# otl.net
KiCad netlist of a schematic drawn in EAGLE
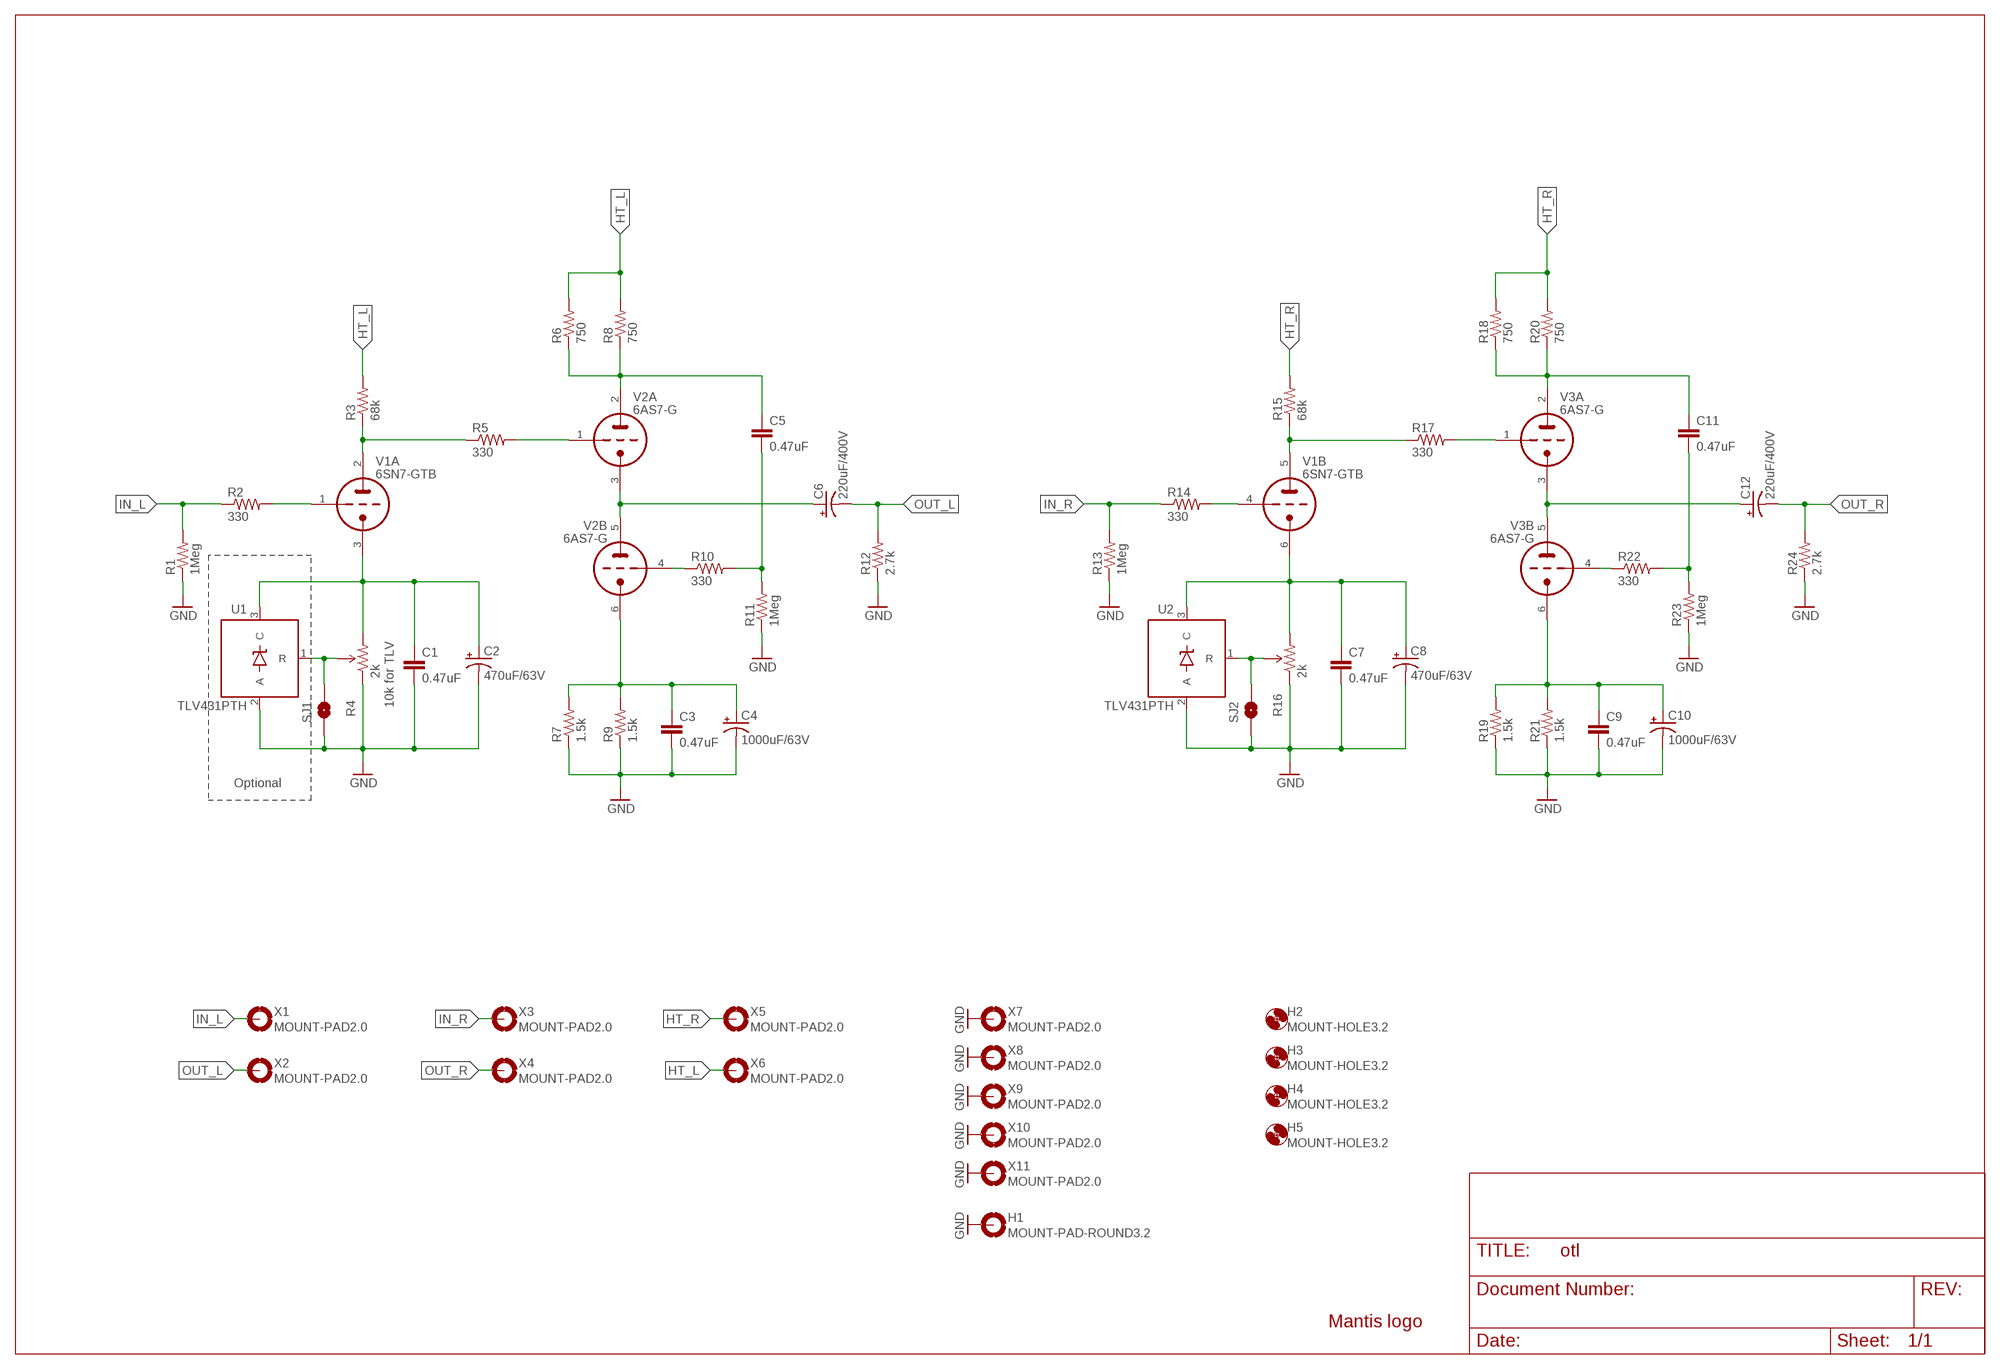
[diagram p0: schematic, sheet 1]

(export (version "E")
  (design (tool "Eeschema 10.0.6"))
  (components
    (comp (ref "C1")
      (value "0.47uF")
      (footprint "eagle-import:C5B5.5")
      (libsource (lib "eagle-import") (part "C5/5.5"))
    )
    (comp (ref "C2")
      (value "470uF/63V")
      (footprint "eagle-import:CPOL-RADIAL-16_7.5")
      (libsource (lib "eagle-import") (part "CAP_POLPTH-16/7.5"))
    )
    (comp (ref "C3")
      (value "0.47uF")
      (footprint "eagle-import:C5B5.5")
      (libsource (lib "eagle-import") (part "C5/5.5"))
    )
    (comp (ref "C4")
      (value "1000uF/63V")
      (footprint "eagle-import:CPOL-RADIAL-16_7.5")
      (libsource (lib "eagle-import") (part "CAP_POLPTH-16/7.5"))
    )
    (comp (ref "C5")
      (value "0.47uF")
      (footprint "eagle-import:C22.5B11")
      (libsource (lib "eagle-import") (part "C22/11"))
    )
    (comp (ref "C6")
      (value "220uF/400V")
      (footprint "eagle-import:CPOL-RADIAL-25_12.5")
      (libsource (lib "eagle-import") (part "CAP_POLPTH-25/12.5"))
    )
    (comp (ref "C7")
      (value "0.47uF")
      (footprint "eagle-import:C5B5.5")
      (libsource (lib "eagle-import") (part "C5/5.5"))
    )
    (comp (ref "C8")
      (value "470uF/63V")
      (footprint "eagle-import:CPOL-RADIAL-16_7.5")
      (libsource (lib "eagle-import") (part "CAP_POLPTH-16/7.5"))
    )
    (comp (ref "C9")
      (value "0.47uF")
      (footprint "eagle-import:C5B5.5")
      (libsource (lib "eagle-import") (part "C5/5.5"))
    )
    (comp (ref "C10")
      (value "1000uF/63V")
      (footprint "eagle-import:CPOL-RADIAL-16_7.5")
      (libsource (lib "eagle-import") (part "CAP_POLPTH-16/7.5"))
    )
    (comp (ref "C11")
      (value "0.47uF")
      (footprint "eagle-import:C22.5B11")
      (libsource (lib "eagle-import") (part "C22/11"))
    )
    (comp (ref "C12")
      (value "220uF/400V")
      (footprint "eagle-import:CPOL-RADIAL-25_12.5")
      (libsource (lib "eagle-import") (part "CAP_POLPTH-25/12.5"))
    )
    (comp (ref "H1")
      (value "MOUNT-PAD-ROUND3.2")
      (footprint "eagle-import:3,2-PAD")
      (libsource (lib "eagle-import") (part "MOUNT-PAD-ROUND3.2"))
    )
    (comp (ref "H2")
      (value "MOUNT-HOLE3.2")
      (footprint "eagle-import:3,2")
      (libsource (lib "eagle-import") (part "MOUNT-HOLE3.2"))
    )
    (comp (ref "H3")
      (value "MOUNT-HOLE3.2")
      (footprint "eagle-import:3,2")
      (libsource (lib "eagle-import") (part "MOUNT-HOLE3.2"))
    )
    (comp (ref "H4")
      (value "MOUNT-HOLE3.2")
      (footprint "eagle-import:3,2")
      (libsource (lib "eagle-import") (part "MOUNT-HOLE3.2"))
    )
    (comp (ref "H5")
      (value "MOUNT-HOLE3.2")
      (footprint "eagle-import:3,2")
      (libsource (lib "eagle-import") (part "MOUNT-HOLE3.2"))
    )
    (comp (ref "LOGO1")
      (value "LOGO-MANTIS")
      (footprint "eagle-import:LOGO-MANTIS")
      (libsource (lib "eagle-import") (part "LOGO-MANTIS"))
    )
    (comp (ref "R1")
      (value "1Meg")
      (footprint "eagle-import:AXIAL-0.4")
      (libsource (lib "eagle-import") (part "RESISTORPTH-1/4W"))
    )
    (comp (ref "R2")
      (value "330")
      (footprint "eagle-import:AXIAL-0.4")
      (libsource (lib "eagle-import") (part "RESISTORPTH-1/4W"))
    )
    (comp (ref "R3")
      (value "68k")
      (footprint "eagle-import:AXIAL-0.8")
      (libsource (lib "eagle-import") (part "RESISTORPTH-2W"))
    )
    (comp (ref "R4")
      (value "2k")
      (footprint "eagle-import:3362U-2")
      (libsource (lib "eagle-import") (part "TRIMPOT3362U-2"))
    )
    (comp (ref "R5")
      (value "330")
      (footprint "eagle-import:AXIAL-0.4")
      (libsource (lib "eagle-import") (part "RESISTORPTH-1/4W"))
    )
    (comp (ref "R6")
      (value "750")
      (footprint "eagle-import:AXIAL-0.8")
      (libsource (lib "eagle-import") (part "RESISTORPTH-2W"))
    )
    (comp (ref "R7")
      (value "1.5k")
      (footprint "eagle-import:AXIAL-0.8")
      (libsource (lib "eagle-import") (part "RESISTORPTH-2W"))
    )
    (comp (ref "R8")
      (value "750")
      (footprint "eagle-import:AXIAL-0.8")
      (libsource (lib "eagle-import") (part "RESISTORPTH-2W"))
    )
    (comp (ref "R9")
      (value "1.5k")
      (footprint "eagle-import:AXIAL-0.8")
      (libsource (lib "eagle-import") (part "RESISTORPTH-2W"))
    )
    (comp (ref "R10")
      (value "330")
      (footprint "eagle-import:AXIAL-0.4")
      (libsource (lib "eagle-import") (part "RESISTORPTH-1/4W"))
    )
    (comp (ref "R11")
      (value "1Meg")
      (footprint "eagle-import:AXIAL-0.4")
      (libsource (lib "eagle-import") (part "RESISTORPTH-1/4W"))
    )
    (comp (ref "R12")
      (value "2.7k")
      (footprint "eagle-import:AXIAL-0.4")
      (libsource (lib "eagle-import") (part "RESISTORPTH-1/4W"))
    )
    (comp (ref "R13")
      (value "1Meg")
      (footprint "eagle-import:AXIAL-0.4")
      (libsource (lib "eagle-import") (part "RESISTORPTH-1/4W"))
    )
    (comp (ref "R14")
      (value "330")
      (footprint "eagle-import:AXIAL-0.4")
      (libsource (lib "eagle-import") (part "RESISTORPTH-1/4W"))
    )
    (comp (ref "R15")
      (value "68k")
      (footprint "eagle-import:AXIAL-0.8")
      (libsource (lib "eagle-import") (part "RESISTORPTH-2W"))
    )
    (comp (ref "R16")
      (value "2k")
      (footprint "eagle-import:3362U-2")
      (libsource (lib "eagle-import") (part "TRIMPOT3362U-2"))
    )
    (comp (ref "R17")
      (value "330")
      (footprint "eagle-import:AXIAL-0.4")
      (libsource (lib "eagle-import") (part "RESISTORPTH-1/4W"))
    )
    (comp (ref "R18")
      (value "750")
      (footprint "eagle-import:AXIAL-0.8")
      (libsource (lib "eagle-import") (part "RESISTORPTH-2W"))
    )
    (comp (ref "R19")
      (value "1.5k")
      (footprint "eagle-import:AXIAL-0.8")
      (libsource (lib "eagle-import") (part "RESISTORPTH-2W"))
    )
    (comp (ref "R20")
      (value "750")
      (footprint "eagle-import:AXIAL-0.8")
      (libsource (lib "eagle-import") (part "RESISTORPTH-2W"))
    )
    (comp (ref "R21")
      (value "1.5k")
      (footprint "eagle-import:AXIAL-0.8")
      (libsource (lib "eagle-import") (part "RESISTORPTH-2W"))
    )
    (comp (ref "R22")
      (value "330")
      (footprint "eagle-import:AXIAL-0.4")
      (libsource (lib "eagle-import") (part "RESISTORPTH-1/4W"))
    )
    (comp (ref "R23")
      (value "1Meg")
      (footprint "eagle-import:AXIAL-0.4")
      (libsource (lib "eagle-import") (part "RESISTORPTH-1/4W"))
    )
    (comp (ref "R24")
      (value "2.7k")
      (footprint "eagle-import:AXIAL-0.4")
      (libsource (lib "eagle-import") (part "RESISTORPTH-1/4W"))
    )
    (comp (ref "SJ1")
      (value "SOLDERJUMPERNO-LARGE")
      (footprint "eagle-import:SJ_2S-NO-LARGE")
      (libsource (lib "eagle-import") (part "SOLDERJUMPERNO-LARGE"))
    )
    (comp (ref "SJ2")
      (value "SOLDERJUMPERNO-LARGE")
      (footprint "eagle-import:SJ_2S-NO-LARGE")
      (libsource (lib "eagle-import") (part "SOLDERJUMPERNO-LARGE"))
    )
    (comp (ref "U1")
      (value "TLV431PTH")
      (footprint "eagle-import:TO-92")
      (libsource (lib "eagle-import") (part "TLV431PTH"))
    )
    (comp (ref "U2")
      (value "TLV431PTH")
      (footprint "eagle-import:TO-92")
      (libsource (lib "eagle-import") (part "TLV431PTH"))
    )
    (comp (ref "V1")
      (value "6SN7-GTB")
      (footprint "eagle-import:OKTAL-OUTLET")
      (libsource (lib "eagle-import") (part "6SN7GT-P-NHOUTLET"))
    )
    (comp (ref "V2")
      (value "6AS7-G")
      (footprint "eagle-import:OKTAL-OUTLET")
      (libsource (lib "eagle-import") (part "6AS7G-P-NHOUTLET"))
    )
    (comp (ref "V3")
      (value "6AS7-G")
      (footprint "eagle-import:OKTAL-OUTLET")
      (libsource (lib "eagle-import") (part "6AS7G-P-NHOUTLET"))
    )
    (comp (ref "X1")
      (value "MOUNT-PAD2.0")
      (footprint "eagle-import:2.0-PAD")
      (libsource (lib "eagle-import") (part "MOUNT-PAD2.0"))
    )
    (comp (ref "X2")
      (value "MOUNT-PAD2.0")
      (footprint "eagle-import:2.0-PAD")
      (libsource (lib "eagle-import") (part "MOUNT-PAD2.0"))
    )
    (comp (ref "X3")
      (value "MOUNT-PAD2.0")
      (footprint "eagle-import:2.0-PAD")
      (libsource (lib "eagle-import") (part "MOUNT-PAD2.0"))
    )
    (comp (ref "X4")
      (value "MOUNT-PAD2.0")
      (footprint "eagle-import:2.0-PAD")
      (libsource (lib "eagle-import") (part "MOUNT-PAD2.0"))
    )
    (comp (ref "X5")
      (value "MOUNT-PAD2.0")
      (footprint "eagle-import:2.0-PAD")
      (libsource (lib "eagle-import") (part "MOUNT-PAD2.0"))
    )
    (comp (ref "X6")
      (value "MOUNT-PAD2.0")
      (footprint "eagle-import:2.0-PAD")
      (libsource (lib "eagle-import") (part "MOUNT-PAD2.0"))
    )
    (comp (ref "X7")
      (value "MOUNT-PAD2.0")
      (footprint "eagle-import:2.0-PAD")
      (libsource (lib "eagle-import") (part "MOUNT-PAD2.0"))
    )
    (comp (ref "X8")
      (value "MOUNT-PAD2.0")
      (footprint "eagle-import:2.0-PAD")
      (libsource (lib "eagle-import") (part "MOUNT-PAD2.0"))
    )
    (comp (ref "X9")
      (value "MOUNT-PAD2.0")
      (footprint "eagle-import:2.0-PAD")
      (libsource (lib "eagle-import") (part "MOUNT-PAD2.0"))
    )
    (comp (ref "X10")
      (value "MOUNT-PAD2.0")
      (footprint "eagle-import:2.0-PAD")
      (libsource (lib "eagle-import") (part "MOUNT-PAD2.0"))
    )
    (comp (ref "X11")
      (value "MOUNT-PAD2.0")
      (footprint "eagle-import:2.0-PAD")
      (libsource (lib "eagle-import") (part "MOUNT-PAD2.0"))
    )
  )
  (nets
    (net (code "1") (name "GND") (class "Default")
      (node (ref "C1") (pin "2") (pinfunction "2_2") (pintype "passive"))
      (node (ref "C10") (pin "2") (pinfunction "-_2") (pintype "passive"))
      (node (ref "C2") (pin "2") (pinfunction "-_2") (pintype "passive"))
      (node (ref "C3") (pin "2") (pinfunction "2_2") (pintype "passive"))
      (node (ref "C4") (pin "2") (pinfunction "-_2") (pintype "passive"))
      (node (ref "C7") (pin "2") (pinfunction "2_2") (pintype "passive"))
      (node (ref "C8") (pin "2") (pinfunction "-_2") (pintype "passive"))
      (node (ref "C9") (pin "2") (pinfunction "2_2") (pintype "passive"))
      (node (ref "H1") (pin "B3,2") (pinfunction "MOUNT_B3,2") (pintype "passive"))
      (node (ref "R1") (pin "P$1") (pinfunction "1_P$1") (pintype "passive"))
      (node (ref "R11") (pin "P$1") (pinfunction "1_P$1") (pintype "passive"))
      (node (ref "R12") (pin "P$1") (pinfunction "1_P$1") (pintype "passive"))
      (node (ref "R13") (pin "P$1") (pinfunction "1_P$1") (pintype "passive"))
      (node (ref "R16") (pin "1") (pinfunction "CCW_1") (pintype "passive"))
      (node (ref "R19") (pin "P$1") (pinfunction "1_P$1") (pintype "passive"))
      (node (ref "R21") (pin "P$1") (pinfunction "1_P$1") (pintype "passive"))
      (node (ref "R23") (pin "P$1") (pinfunction "1_P$1") (pintype "passive"))
      (node (ref "R24") (pin "P$1") (pinfunction "1_P$1") (pintype "passive"))
      (node (ref "R4") (pin "1") (pinfunction "CCW_1") (pintype "passive"))
      (node (ref "R7") (pin "P$1") (pinfunction "1_P$1") (pintype "passive"))
      (node (ref "R9") (pin "P$1") (pinfunction "1_P$1") (pintype "passive"))
      (node (ref "SJ1") (pin "1") (pinfunction "1_1") (pintype "passive"))
      (node (ref "SJ2") (pin "1") (pinfunction "1_1") (pintype "passive"))
      (node (ref "U1") (pin "2") (pinfunction "A_2") (pintype "bidirectional"))
      (node (ref "U2") (pin "2") (pinfunction "A_2") (pintype "bidirectional"))
      (node (ref "X10") (pin "P$1") (pinfunction "MOUNT_P$1") (pintype "passive"))
      (node (ref "X11") (pin "P$1") (pinfunction "MOUNT_P$1") (pintype "passive"))
      (node (ref "X7") (pin "P$1") (pinfunction "MOUNT_P$1") (pintype "passive"))
      (node (ref "X8") (pin "P$1") (pinfunction "MOUNT_P$1") (pintype "passive"))
      (node (ref "X9") (pin "P$1") (pinfunction "MOUNT_P$1") (pintype "passive"))
    )
    (net (code "2") (name "HT_L") (class "Default")
      (node (ref "R3") (pin "P$2") (pinfunction "2_P$2") (pintype "passive"))
      (node (ref "R6") (pin "P$2") (pinfunction "2_P$2") (pintype "passive"))
      (node (ref "R8") (pin "P$2") (pinfunction "2_P$2") (pintype "passive"))
      (node (ref "X6") (pin "P$1") (pinfunction "MOUNT_P$1") (pintype "passive"))
    )
    (net (code "3") (name "HT_R") (class "Default")
      (node (ref "R15") (pin "P$2") (pinfunction "2_P$2") (pintype "passive"))
      (node (ref "R18") (pin "P$2") (pinfunction "2_P$2") (pintype "passive"))
      (node (ref "R20") (pin "P$2") (pinfunction "2_P$2") (pintype "passive"))
      (node (ref "X5") (pin "P$1") (pinfunction "MOUNT_P$1") (pintype "passive"))
    )
    (net (code "4") (name "IN_L") (class "Default")
      (node (ref "R1") (pin "P$2") (pinfunction "2_P$2") (pintype "passive"))
      (node (ref "R2") (pin "P$1") (pinfunction "1_P$1") (pintype "passive"))
      (node (ref "X1") (pin "P$1") (pinfunction "MOUNT_P$1") (pintype "passive"))
    )
    (net (code "5") (name "IN_R") (class "Default")
      (node (ref "R13") (pin "P$2") (pinfunction "2_P$2") (pintype "passive"))
      (node (ref "R14") (pin "P$1") (pinfunction "1_P$1") (pintype "passive"))
      (node (ref "X3") (pin "P$1") (pinfunction "MOUNT_P$1") (pintype "passive"))
    )
    (net (code "6") (name "Net-(C2-+)") (class "Default")
      (node (ref "C1") (pin "1") (pinfunction "1_1") (pintype "passive"))
      (node (ref "C2") (pin "1") (pinfunction "+_1") (pintype "passive"))
      (node (ref "R4") (pin "3") (pinfunction "CW_3") (pintype "passive"))
      (node (ref "U1") (pin "3") (pinfunction "C_3") (pintype "bidirectional"))
      (node (ref "V1") (pin "3") (pinfunction "TK_3") (pintype "passive"))
    )
    (net (code "7") (name "Net-(C4-+)") (class "Default")
      (node (ref "C3") (pin "1") (pinfunction "1_1") (pintype "passive"))
      (node (ref "C4") (pin "1") (pinfunction "+_1") (pintype "passive"))
      (node (ref "R7") (pin "P$2") (pinfunction "2_P$2") (pintype "passive"))
      (node (ref "R9") (pin "P$2") (pinfunction "2_P$2") (pintype "passive"))
      (node (ref "V2") (pin "6") (pinfunction "TK_6") (pintype "passive"))
    )
    (net (code "8") (name "Net-(C6-+)") (class "Default")
      (node (ref "C6") (pin "1") (pinfunction "+_1") (pintype "passive"))
      (node (ref "V2") (pin "3") (pinfunction "TK_3") (pintype "passive"))
      (node (ref "V2") (pin "5") (pinfunction "TA_5") (pintype "passive"))
    )
    (net (code "9") (name "Net-(C8-+)") (class "Default")
      (node (ref "C7") (pin "1") (pinfunction "1_1") (pintype "passive"))
      (node (ref "C8") (pin "1") (pinfunction "+_1") (pintype "passive"))
      (node (ref "R16") (pin "3") (pinfunction "CW_3") (pintype "passive"))
      (node (ref "U2") (pin "3") (pinfunction "C_3") (pintype "bidirectional"))
      (node (ref "V1") (pin "6") (pinfunction "TK_6") (pintype "passive"))
    )
    (net (code "10") (name "Net-(C10-+)") (class "Default")
      (node (ref "C10") (pin "1") (pinfunction "+_1") (pintype "passive"))
      (node (ref "C9") (pin "1") (pinfunction "1_1") (pintype "passive"))
      (node (ref "R19") (pin "P$2") (pinfunction "2_P$2") (pintype "passive"))
      (node (ref "R21") (pin "P$2") (pinfunction "2_P$2") (pintype "passive"))
      (node (ref "V3") (pin "6") (pinfunction "TK_6") (pintype "passive"))
    )
    (net (code "11") (name "Net-(C12-+)") (class "Default")
      (node (ref "C12") (pin "1") (pinfunction "+_1") (pintype "passive"))
      (node (ref "V3") (pin "3") (pinfunction "TK_3") (pintype "passive"))
      (node (ref "V3") (pin "5") (pinfunction "TA_5") (pintype "passive"))
    )
    (net (code "12") (name "Net-(R2-2)") (class "Default")
      (node (ref "R2") (pin "P$2") (pinfunction "2_P$2") (pintype "passive"))
      (node (ref "V1") (pin "1") (pinfunction "TG_1") (pintype "passive"))
    )
    (net (code "13") (name "Net-(R3-1)") (class "Default")
      (node (ref "R3") (pin "P$1") (pinfunction "1_P$1") (pintype "passive"))
      (node (ref "R5") (pin "P$1") (pinfunction "1_P$1") (pintype "passive"))
      (node (ref "V1") (pin "2") (pinfunction "TA_2") (pintype "passive"))
    )
    (net (code "14") (name "Net-(R4-WIPER)") (class "Default")
      (node (ref "R4") (pin "2") (pinfunction "WIPER_2") (pintype "passive"))
      (node (ref "SJ1") (pin "2") (pinfunction "2_2") (pintype "passive"))
      (node (ref "U1") (pin "1") (pinfunction "R_1") (pintype "bidirectional"))
    )
    (net (code "15") (name "Net-(R5-2)") (class "Default")
      (node (ref "R5") (pin "P$2") (pinfunction "2_P$2") (pintype "passive"))
      (node (ref "V2") (pin "1") (pinfunction "TG_1") (pintype "passive"))
    )
    (net (code "16") (name "Net-(R6-1)") (class "Default")
      (node (ref "C5") (pin "1") (pinfunction "1_1") (pintype "passive"))
      (node (ref "R6") (pin "P$1") (pinfunction "1_P$1") (pintype "passive"))
      (node (ref "R8") (pin "P$1") (pinfunction "1_P$1") (pintype "passive"))
      (node (ref "V2") (pin "2") (pinfunction "TA_2") (pintype "passive"))
    )
    (net (code "17") (name "Net-(R10-1)") (class "Default")
      (node (ref "R10") (pin "P$1") (pinfunction "1_P$1") (pintype "passive"))
      (node (ref "V2") (pin "4") (pinfunction "TG_4") (pintype "passive"))
    )
    (net (code "18") (name "Net-(R10-2)") (class "Default")
      (node (ref "C5") (pin "2") (pinfunction "2_2") (pintype "passive"))
      (node (ref "R10") (pin "P$2") (pinfunction "2_P$2") (pintype "passive"))
      (node (ref "R11") (pin "P$2") (pinfunction "2_P$2") (pintype "passive"))
    )
    (net (code "19") (name "Net-(R14-2)") (class "Default")
      (node (ref "R14") (pin "P$2") (pinfunction "2_P$2") (pintype "passive"))
      (node (ref "V1") (pin "4") (pinfunction "TG_4") (pintype "passive"))
    )
    (net (code "20") (name "Net-(R15-1)") (class "Default")
      (node (ref "R15") (pin "P$1") (pinfunction "1_P$1") (pintype "passive"))
      (node (ref "R17") (pin "P$1") (pinfunction "1_P$1") (pintype "passive"))
      (node (ref "V1") (pin "5") (pinfunction "TA_5") (pintype "passive"))
    )
    (net (code "21") (name "Net-(R16-WIPER)") (class "Default")
      (node (ref "R16") (pin "2") (pinfunction "WIPER_2") (pintype "passive"))
      (node (ref "SJ2") (pin "2") (pinfunction "2_2") (pintype "passive"))
      (node (ref "U2") (pin "1") (pinfunction "R_1") (pintype "bidirectional"))
    )
    (net (code "22") (name "Net-(R17-2)") (class "Default")
      (node (ref "R17") (pin "P$2") (pinfunction "2_P$2") (pintype "passive"))
      (node (ref "V3") (pin "1") (pinfunction "TG_1") (pintype "passive"))
    )
    (net (code "23") (name "Net-(R18-1)") (class "Default")
      (node (ref "C11") (pin "1") (pinfunction "1_1") (pintype "passive"))
      (node (ref "R18") (pin "P$1") (pinfunction "1_P$1") (pintype "passive"))
      (node (ref "R20") (pin "P$1") (pinfunction "1_P$1") (pintype "passive"))
      (node (ref "V3") (pin "2") (pinfunction "TA_2") (pintype "passive"))
    )
    (net (code "24") (name "Net-(R22-1)") (class "Default")
      (node (ref "R22") (pin "P$1") (pinfunction "1_P$1") (pintype "passive"))
      (node (ref "V3") (pin "4") (pinfunction "TG_4") (pintype "passive"))
    )
    (net (code "25") (name "Net-(R22-2)") (class "Default")
      (node (ref "C11") (pin "2") (pinfunction "2_2") (pintype "passive"))
      (node (ref "R22") (pin "P$2") (pinfunction "2_P$2") (pintype "passive"))
      (node (ref "R23") (pin "P$2") (pinfunction "2_P$2") (pintype "passive"))
    )
    (net (code "26") (name "OUT_L") (class "Default")
      (node (ref "C6") (pin "2") (pinfunction "-_2") (pintype "passive"))
      (node (ref "R12") (pin "P$2") (pinfunction "2_P$2") (pintype "passive"))
      (node (ref "X2") (pin "P$1") (pinfunction "MOUNT_P$1") (pintype "passive"))
    )
    (net (code "27") (name "OUT_R") (class "Default")
      (node (ref "C12") (pin "2") (pinfunction "-_2") (pintype "passive"))
      (node (ref "R24") (pin "P$2") (pinfunction "2_P$2") (pintype "passive"))
      (node (ref "X4") (pin "P$1") (pinfunction "MOUNT_P$1") (pintype "passive"))
    )
  )
)
